# ESP12.net
KiCad netlist of a schematic drawn in Altium Designer
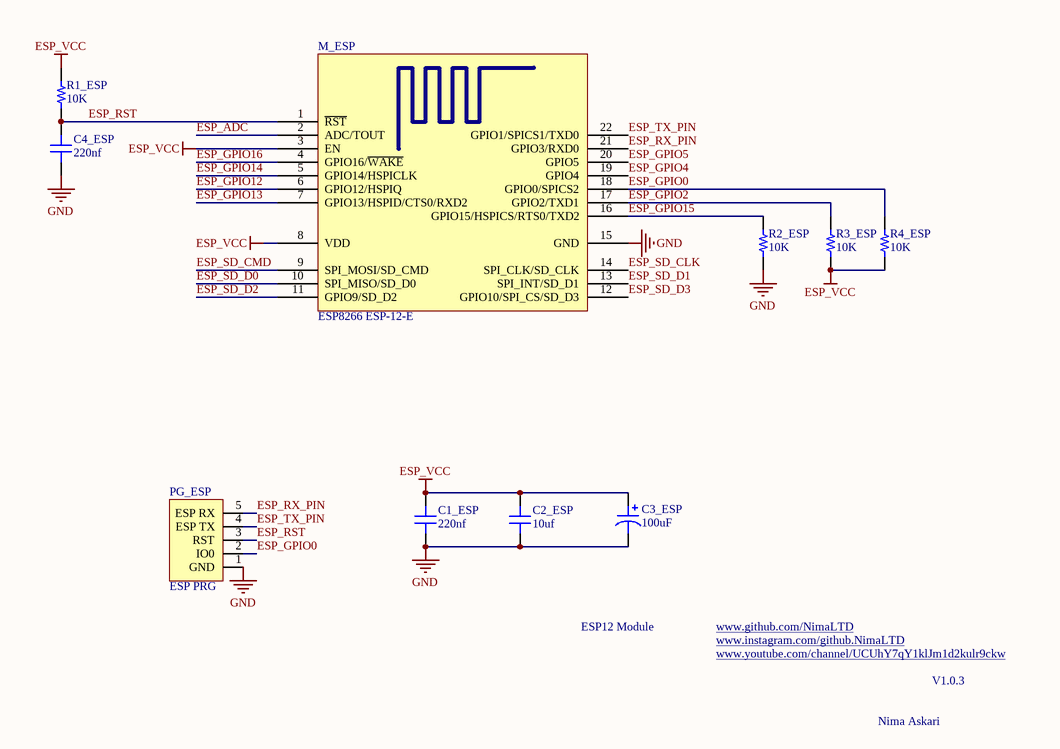
[diagram p0: ESP12.SchDoc]

(export (version "E")
  (design (tool "Eeschema 10.0.6"))
  (components
    (comp (ref "C1_ESP")
      (value "220nf")
      (footprint "CAP 0805")
      (description "SMT Capacitor")
      (libsource (lib "CAPACITOR") (part "Cap SMD 0805"))
    )
    (comp (ref "C2_ESP")
      (value "10uf")
      (footprint "CAP 0805")
      (description "SMT Capacitor")
      (libsource (lib "CAPACITOR") (part "Cap SMD 0805"))
    )
    (comp (ref "C3_ESP")
      (value "100uF")
      (footprint "CAP AL SMD D6 H6")
      (description "SMT Polarised Capacitor")
      (libsource (lib "CAPACITOR") (part "Pol Cap SMD AL D6 H6"))
    )
    (comp (ref "C4_ESP")
      (value "220nf")
      (footprint "CAP 0805")
      (description "SMT Capacitor")
      (libsource (lib "CAPACITOR") (part "Cap SMD 0805"))
    )
    (comp (ref "M_ESP")
      (value "ESP8266 ESP-12-E")
      (footprint "M_ESP12")
      (libsource (lib "MODULE") (part "ESP8266 ESP-12-E"))
    )
    (comp (ref "PG_ESP")
      (value "ESP PRG")
      (footprint "HDR2_M_1X5")
      (libsource (lib "CONNECTOR") (part "ESP PRG P2.0"))
    )
    (comp (ref "R1_ESP")
      (value "10K")
      (footprint "RES 0805")
      (description "SMD Resistor")
      (libsource (lib "RESISTOR") (part "Res SMD 0805"))
    )
    (comp (ref "R2_ESP")
      (value "10K")
      (footprint "RES 0805")
      (description "SMD Resistor")
      (libsource (lib "RESISTOR") (part "Res SMD 0805"))
    )
    (comp (ref "R3_ESP")
      (value "10K")
      (footprint "RES 0805")
      (description "SMD Resistor")
      (libsource (lib "RESISTOR") (part "Res SMD 0805"))
    )
    (comp (ref "R4_ESP")
      (value "10K")
      (footprint "RES 0805")
      (description "SMD Resistor")
      (libsource (lib "RESISTOR") (part "Res SMD 0805"))
    )
  )
  (nets
    (net (code "1") (name "/ESP_ADC") (class "Default")
      (node (ref "M_ESP") (pin "2") (pinfunction "ADC/TOUT_2") (pintype "passive"))
    )
    (net (code "2") (name "/ESP_GPIO0") (class "Default")
      (node (ref "M_ESP") (pin "18") (pinfunction "GPIO0/SPICS2_18") (pintype "passive"))
      (node (ref "PG_ESP") (pin "2") (pinfunction "IO0_2") (pintype "passive"))
      (node (ref "R4_ESP") (pin "1") (pinfunction "1_1") (pintype "passive"))
    )
    (net (code "3") (name "/ESP_GPIO2") (class "Default")
      (node (ref "M_ESP") (pin "17") (pinfunction "GPIO2/TXD1_17") (pintype "passive"))
      (node (ref "R3_ESP") (pin "1") (pinfunction "1_1") (pintype "passive"))
    )
    (net (code "4") (name "/ESP_GPIO4") (class "Default")
      (node (ref "M_ESP") (pin "19") (pinfunction "GPIO4_19") (pintype "passive"))
    )
    (net (code "5") (name "/ESP_GPIO5") (class "Default")
      (node (ref "M_ESP") (pin "20") (pinfunction "GPIO5_20") (pintype "passive"))
    )
    (net (code "6") (name "/ESP_GPIO12") (class "Default")
      (node (ref "M_ESP") (pin "6") (pinfunction "GPIO12/HSPIQ_6") (pintype "passive"))
    )
    (net (code "7") (name "/ESP_GPIO13") (class "Default")
      (node (ref "M_ESP") (pin "7") (pinfunction "GPIO13/HSPID/CTS0/RXD2_7") (pintype "passive"))
    )
    (net (code "8") (name "/ESP_GPIO14") (class "Default")
      (node (ref "M_ESP") (pin "5") (pinfunction "GPIO14/HSPICLK_5") (pintype "passive"))
    )
    (net (code "9") (name "/ESP_GPIO15") (class "Default")
      (node (ref "M_ESP") (pin "16") (pinfunction "GPIO15/HSPICS/RTS0/TXD2_16") (pintype "passive"))
      (node (ref "R2_ESP") (pin "1") (pinfunction "1_1") (pintype "passive"))
    )
    (net (code "10") (name "/ESP_GPIO16") (class "Default")
      (node (ref "M_ESP") (pin "4") (pinfunction "GPIO16/~{WAKE}_4") (pintype "passive"))
    )
    (net (code "11") (name "/ESP_RST") (class "Default")
      (node (ref "C4_ESP") (pin "2") (pinfunction "2_2") (pintype "passive"))
      (node (ref "M_ESP") (pin "1") (pinfunction "~{RST}_1") (pintype "passive"))
      (node (ref "PG_ESP") (pin "3") (pinfunction "RST_3") (pintype "passive"))
      (node (ref "R1_ESP") (pin "1") (pinfunction "1_1") (pintype "passive"))
    )
    (net (code "12") (name "/ESP_RX_PIN") (class "Default")
      (node (ref "M_ESP") (pin "21") (pinfunction "GPIO3/RXD0_21") (pintype "passive"))
      (node (ref "PG_ESP") (pin "5") (pinfunction "ESP_RX_5") (pintype "passive"))
    )
    (net (code "13") (name "/ESP_SD_CLK") (class "Default")
      (node (ref "M_ESP") (pin "14") (pinfunction "SPI_CLK/SD_CLK_14") (pintype "passive"))
    )
    (net (code "14") (name "/ESP_SD_CMD") (class "Default")
      (node (ref "M_ESP") (pin "9") (pinfunction "SPI_MOSI/SD_CMD_9") (pintype "passive"))
    )
    (net (code "15") (name "/ESP_SD_D0") (class "Default")
      (node (ref "M_ESP") (pin "10") (pinfunction "SPI_MISO/SD_D0_10") (pintype "passive"))
    )
    (net (code "16") (name "/ESP_SD_D1") (class "Default")
      (node (ref "M_ESP") (pin "13") (pinfunction "SPI_INT/SD_D1_13") (pintype "passive"))
    )
    (net (code "17") (name "/ESP_SD_D2") (class "Default")
      (node (ref "M_ESP") (pin "11") (pinfunction "GPIO9/SD_D2_11") (pintype "passive"))
    )
    (net (code "18") (name "/ESP_SD_D3") (class "Default")
      (node (ref "M_ESP") (pin "12") (pinfunction "GPIO10/SPI_CS/SD_D3_12") (pintype "passive"))
    )
    (net (code "19") (name "/ESP_TX_PIN") (class "Default")
      (node (ref "M_ESP") (pin "22") (pinfunction "GPIO1/SPICS1/TXD0_22") (pintype "passive"))
      (node (ref "PG_ESP") (pin "4") (pinfunction "ESP_TX_4") (pintype "passive"))
    )
    (net (code "20") (name "ESP_VCC") (class "Default")
      (node (ref "C1_ESP") (pin "2") (pinfunction "2_2") (pintype "passive"))
      (node (ref "C2_ESP") (pin "2") (pinfunction "2_2") (pintype "passive"))
      (node (ref "C3_ESP") (pin "1") (pinfunction "1_1") (pintype "passive"))
      (node (ref "M_ESP") (pin "3") (pinfunction "EN_3") (pintype "passive"))
      (node (ref "M_ESP") (pin "8") (pinfunction "VDD_8") (pintype "passive"))
      (node (ref "R1_ESP") (pin "2") (pinfunction "2_2") (pintype "passive"))
      (node (ref "R3_ESP") (pin "2") (pinfunction "2_2") (pintype "passive"))
      (node (ref "R4_ESP") (pin "2") (pinfunction "2_2") (pintype "passive"))
    )
    (net (code "21") (name "GND") (class "Default")
      (node (ref "C1_ESP") (pin "1") (pinfunction "1_1") (pintype "passive"))
      (node (ref "C2_ESP") (pin "1") (pinfunction "1_1") (pintype "passive"))
      (node (ref "C3_ESP") (pin "2") (pinfunction "2_2") (pintype "passive"))
      (node (ref "C4_ESP") (pin "1") (pinfunction "1_1") (pintype "passive"))
      (node (ref "M_ESP") (pin "15") (pinfunction "GND_15") (pintype "passive"))
      (node (ref "PG_ESP") (pin "1") (pinfunction "GND_1") (pintype "passive"))
      (node (ref "R2_ESP") (pin "2") (pinfunction "2_2") (pintype "passive"))
    )
  )
)
